# bolid-inputs-hv.net
KiCad netlist of a schematic drawn in Altium Designer
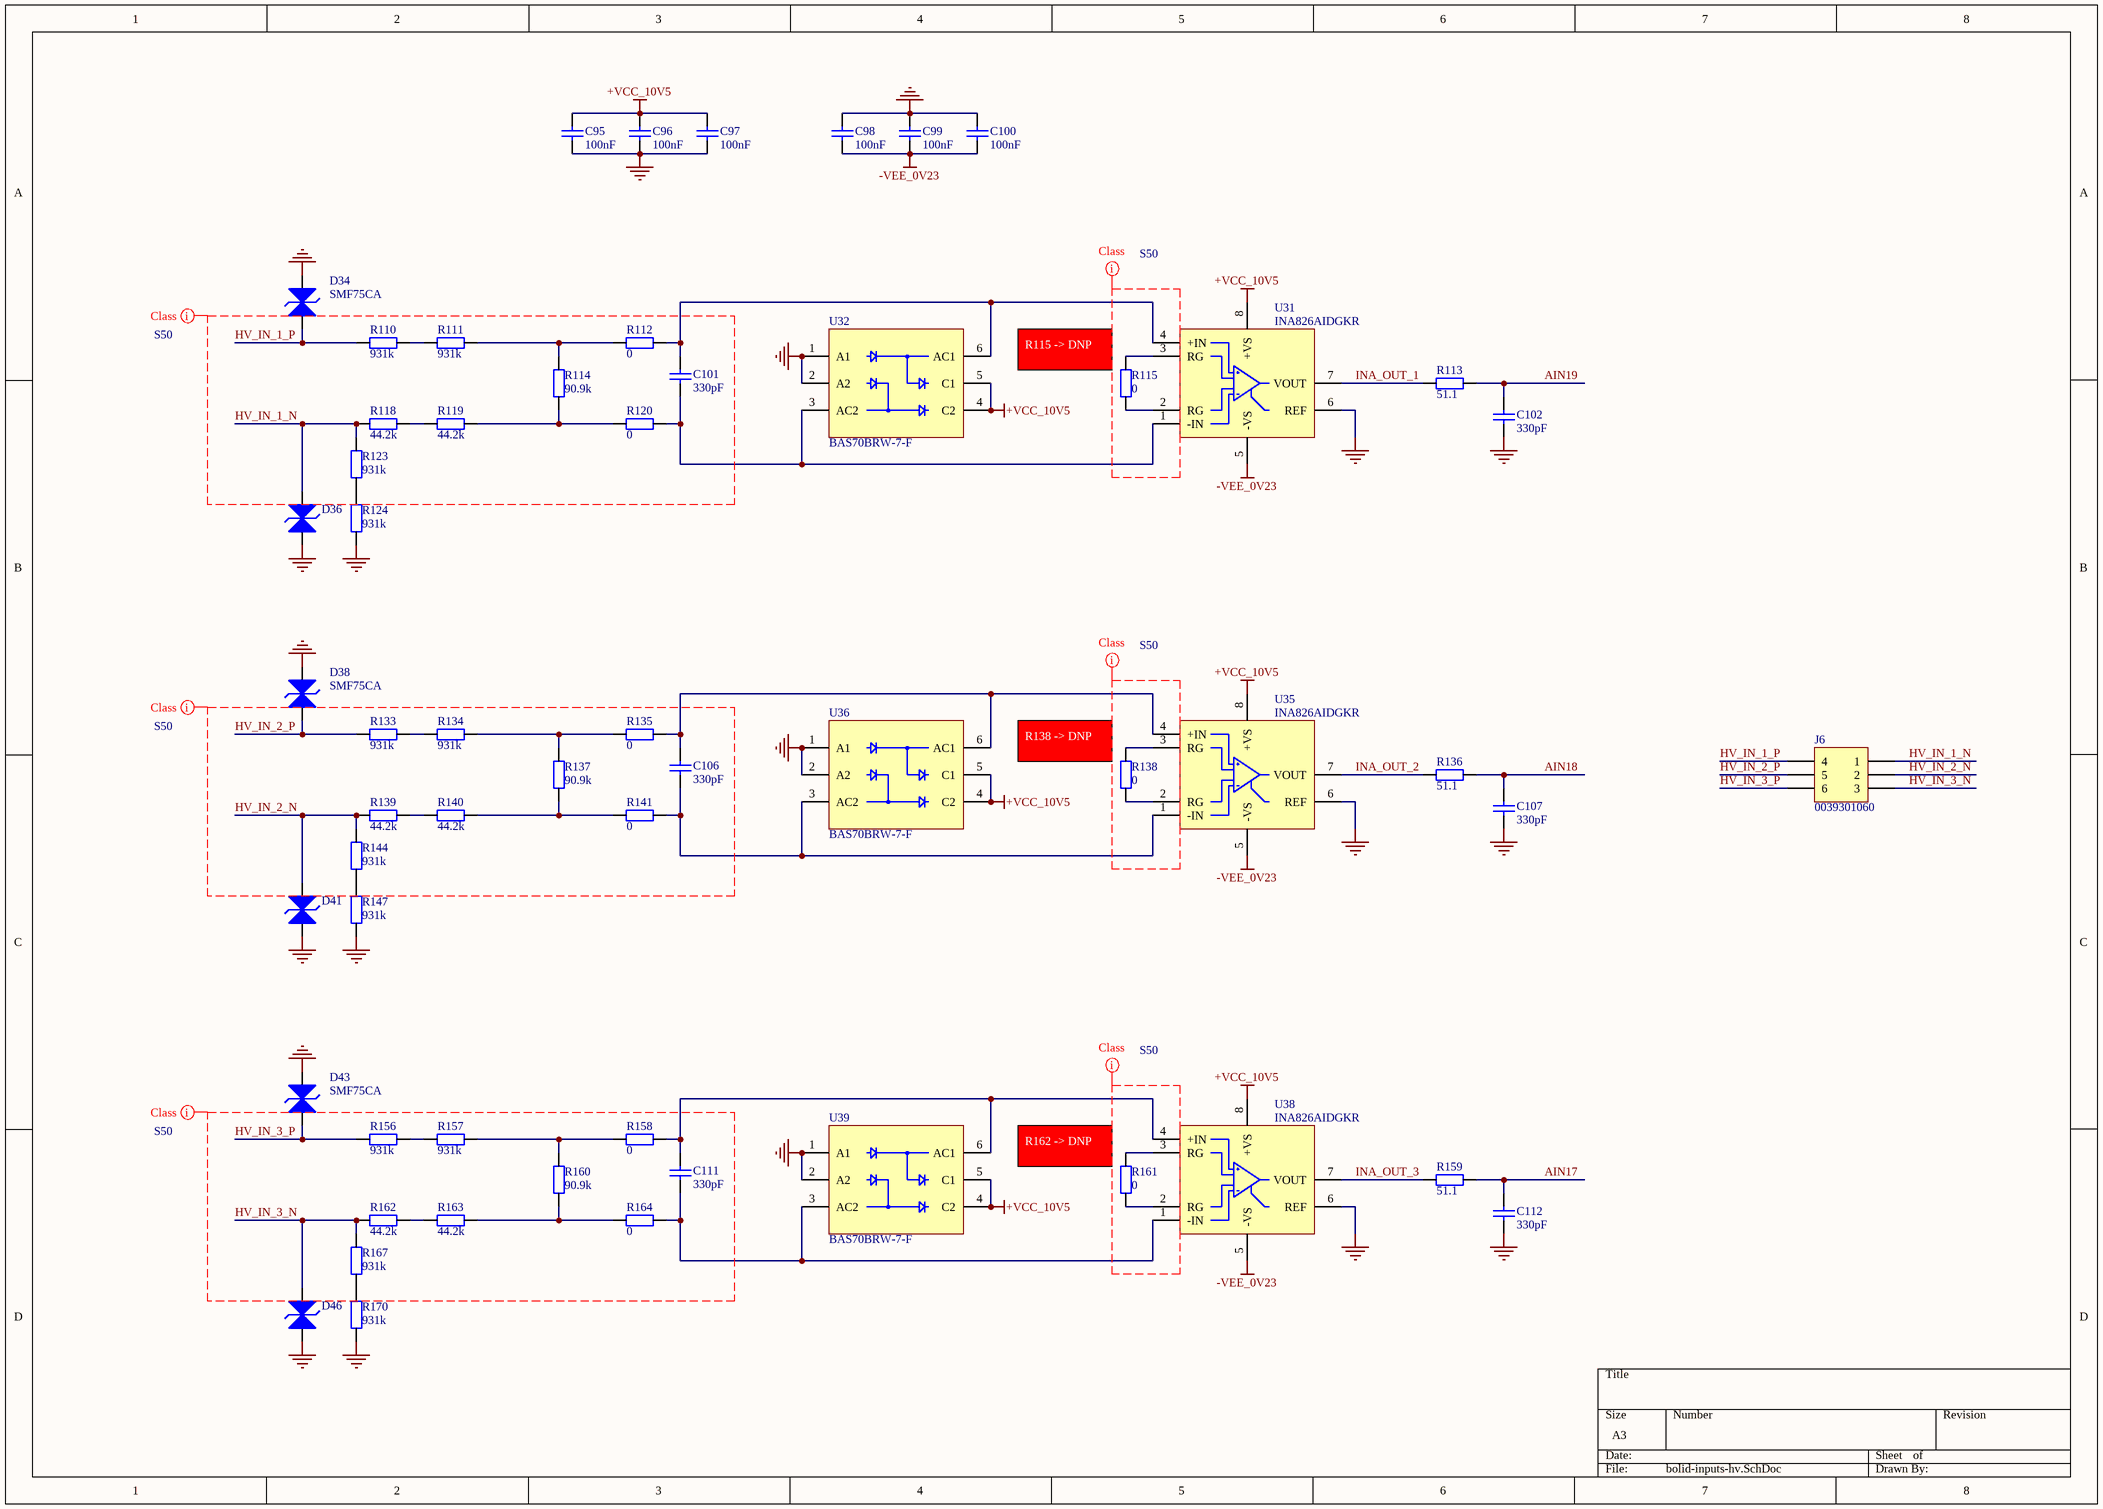
[diagram p0: bolid-inputs-hv.SchDoc]

(export (version "E")
  (design (tool "Eeschema 10.0.6"))
  (components
    (comp (ref "C95")
      (value "GRM155R71H104KE14D")
      (footprint "C0402-CAPC100X50X55L22 - Tayio Yuden TDK")
      (description "MLCC 0402 (1005) 100nF 10% 50V X7R")
      (fields
        (field (name "MANUFACTURER") "Murata Electronics")
        (field (name "TOLERANCE") "10 %")
        (field (name "VALUE DISPLAYED") "100nF")
      )
      (libsource (lib "capacitors2") (part "GRM155R71H104KE14D"))
    )
    (comp (ref "C96")
      (value "GRM155R71H104KE14D")
      (footprint "C0402-CAPC100X50X55L22 - Tayio Yuden TDK")
      (description "MLCC 0402 (1005) 100nF 10% 50V X7R")
      (fields
        (field (name "MANUFACTURER") "Murata Electronics")
        (field (name "TOLERANCE") "10 %")
        (field (name "VALUE DISPLAYED") "100nF")
      )
      (libsource (lib "capacitors2") (part "GRM155R71H104KE14D"))
    )
    (comp (ref "C97")
      (value "GRM155R71H104KE14D")
      (footprint "C0402-CAPC100X50X55L22 - Tayio Yuden TDK")
      (description "MLCC 0402 (1005) 100nF 10% 50V X7R")
      (fields
        (field (name "MANUFACTURER") "Murata Electronics")
        (field (name "TOLERANCE") "10 %")
        (field (name "VALUE DISPLAYED") "100nF")
      )
      (libsource (lib "capacitors2") (part "GRM155R71H104KE14D"))
    )
    (comp (ref "C98")
      (value "GRM155R71H104KE14D")
      (footprint "C0402-CAPC100X50X55L22 - Tayio Yuden TDK")
      (description "MLCC 0402 (1005) 100nF 10% 50V X7R")
      (fields
        (field (name "MANUFACTURER") "Murata Electronics")
        (field (name "TOLERANCE") "10 %")
        (field (name "VALUE DISPLAYED") "100nF")
      )
      (libsource (lib "capacitors2") (part "GRM155R71H104KE14D"))
    )
    (comp (ref "C99")
      (value "GRM155R71H104KE14D")
      (footprint "C0402-CAPC100X50X55L22 - Tayio Yuden TDK")
      (description "MLCC 0402 (1005) 100nF 10% 50V X7R")
      (fields
        (field (name "MANUFACTURER") "Murata Electronics")
        (field (name "TOLERANCE") "10 %")
        (field (name "VALUE DISPLAYED") "100nF")
      )
      (libsource (lib "capacitors2") (part "GRM155R71H104KE14D"))
    )
    (comp (ref "C100")
      (value "GRM155R71H104KE14D")
      (footprint "C0402-CAPC100X50X55L22 - Tayio Yuden TDK")
      (description "MLCC 0402 (1005) 100nF 10% 50V X7R")
      (fields
        (field (name "MANUFACTURER") "Murata Electronics")
        (field (name "TOLERANCE") "10 %")
        (field (name "VALUE DISPLAYED") "100nF")
      )
      (libsource (lib "capacitors2") (part "GRM155R71H104KE14D"))
    )
    (comp (ref "C101")
      (value "C0402C331J5GAC")
      (footprint "C0402-CAPC100X50X55L22 - Tayio Yuden TDK")
      (description "MLCC 0402 (1005) 330pF 5% 50V C0G (N0P)")
      (fields
        (field (name "MANUFACTURER") "KEMET")
        (field (name "TOLERANCE") "5%")
        (field (name "VALUE DISPLAYED") "330pF")
      )
      (libsource (lib "capacitors2") (part "C0402C331J5GAC"))
    )
    (comp (ref "C102")
      (value "C0402C331J5GAC")
      (footprint "C0402-CAPC100X50X55L22 - Tayio Yuden TDK")
      (description "MLCC 0402 (1005) 330pF 5% 50V C0G (N0P)")
      (fields
        (field (name "MANUFACTURER") "KEMET")
        (field (name "TOLERANCE") "5%")
        (field (name "VALUE DISPLAYED") "330pF")
      )
      (libsource (lib "capacitors2") (part "C0402C331J5GAC"))
    )
    (comp (ref "C106")
      (value "C0402C331J5GAC")
      (footprint "C0402-CAPC100X50X55L22 - Tayio Yuden TDK")
      (description "MLCC 0402 (1005) 330pF 5% 50V C0G (N0P)")
      (fields
        (field (name "MANUFACTURER") "KEMET")
        (field (name "TOLERANCE") "5%")
        (field (name "VALUE DISPLAYED") "330pF")
      )
      (libsource (lib "capacitors2") (part "C0402C331J5GAC"))
    )
    (comp (ref "C107")
      (value "C0402C331J5GAC")
      (footprint "C0402-CAPC100X50X55L22 - Tayio Yuden TDK")
      (description "MLCC 0402 (1005) 330pF 5% 50V C0G (N0P)")
      (fields
        (field (name "MANUFACTURER") "KEMET")
        (field (name "TOLERANCE") "5%")
        (field (name "VALUE DISPLAYED") "330pF")
      )
      (libsource (lib "capacitors2") (part "C0402C331J5GAC"))
    )
    (comp (ref "C111")
      (value "C0402C331J5GAC")
      (footprint "C0402-CAPC100X50X55L22 - Tayio Yuden TDK")
      (description "MLCC 0402 (1005) 330pF 5% 50V C0G (N0P)")
      (fields
        (field (name "MANUFACTURER") "KEMET")
        (field (name "TOLERANCE") "5%")
        (field (name "VALUE DISPLAYED") "330pF")
      )
      (libsource (lib "capacitors2") (part "C0402C331J5GAC"))
    )
    (comp (ref "C112")
      (value "C0402C331J5GAC")
      (footprint "C0402-CAPC100X50X55L22 - Tayio Yuden TDK")
      (description "MLCC 0402 (1005) 330pF 5% 50V C0G (N0P)")
      (fields
        (field (name "MANUFACTURER") "KEMET")
        (field (name "TOLERANCE") "5%")
        (field (name "VALUE DISPLAYED") "330pF")
      )
      (libsource (lib "capacitors2") (part "C0402C331J5GAC"))
    )
    (comp (ref "D34")
      (value "SMF75CA")
      (footprint "SOD-123FL SODFL365X110-2N - BIDIRECTIONAL - Littelfuse")
      (fields (field (name "MANUFACTURER") "Littelfuse"))
      (libsource (lib "semiconductors2") (part "SMF75CA"))
    )
    (comp (ref "D36")
      (value "SMF75CA")
      (footprint "SOD-123FL SODFL365X110-2N - BIDIRECTIONAL - Littelfuse")
      (fields (field (name "MANUFACTURER") "Littelfuse"))
      (libsource (lib "semiconductors2") (part "SMF75CA"))
    )
    (comp (ref "D38")
      (value "SMF75CA")
      (footprint "SOD-123FL SODFL365X110-2N - BIDIRECTIONAL - Littelfuse")
      (fields (field (name "MANUFACTURER") "Littelfuse"))
      (libsource (lib "semiconductors2") (part "SMF75CA"))
    )
    (comp (ref "D41")
      (value "SMF75CA")
      (footprint "SOD-123FL SODFL365X110-2N - BIDIRECTIONAL - Littelfuse")
      (fields (field (name "MANUFACTURER") "Littelfuse"))
      (libsource (lib "semiconductors2") (part "SMF75CA"))
    )
    (comp (ref "D43")
      (value "SMF75CA")
      (footprint "SOD-123FL SODFL365X110-2N - BIDIRECTIONAL - Littelfuse")
      (fields (field (name "MANUFACTURER") "Littelfuse"))
      (libsource (lib "semiconductors2") (part "SMF75CA"))
    )
    (comp (ref "D46")
      (value "SMF75CA")
      (footprint "SOD-123FL SODFL365X110-2N - BIDIRECTIONAL - Littelfuse")
      (fields (field (name "MANUFACTURER") "Littelfuse"))
      (libsource (lib "semiconductors2") (part "SMF75CA"))
    )
    (comp (ref "J6")
      (value "0039301060")
      (footprint "MOLEX Mini-Fit Jr 039301060 2x3 PEG")
      (fields (field (name "MANUFACTURER") "Molex"))
      (libsource (lib "connectors2") (part "039301060"))
    )
    (comp (ref "R110")
      (value "931k")
      (footprint "R0603-RESC160X80X55L30N")
      (description "RES 0603 (1608) 931.0k 1% 0.100W 50V Thick Film")
      (fields
        (field (name "MANUFACTURER") "Yageo")
        (field (name "MANUFACTURER PART NUMBER") "RC0603FR-07931KL")
      )
      (libsource (lib "resistors2") (part "RC0603FR-07931KL"))
    )
    (comp (ref "R111")
      (value "931k")
      (footprint "R0603-RESC160X80X55L30N")
      (description "RES 0603 (1608) 931.0k 1% 0.100W 50V Thick Film")
      (fields
        (field (name "MANUFACTURER") "Yageo")
        (field (name "MANUFACTURER PART NUMBER") "RC0603FR-07931KL")
      )
      (libsource (lib "resistors2") (part "RC0603FR-07931KL"))
    )
    (comp (ref "R112")
      (value "0")
      (footprint "R0402-RESC100X50X40L22N")
      (description "RES 0402 (1005) 0.00 ohm 1% 0.0625W 50V Thick Film")
      (fields
        (field (name "MANUFACTURER") "Yageo")
        (field (name "MANUFACTURER PART NUMBER") "RC0402JR-7D0RL")
      )
      (libsource (lib "resistors2") (part "RC0402JR-7D0RL"))
    )
    (comp (ref "R113")
      (value "51.1")
      (footprint "R0402-RESC100X50X40L22N")
      (description "RES 0402 (1005) 51.1 ohm 1% 0.0625W 50V Thick Film")
      (fields
        (field (name "MANUFACTURER") "Yageo")
        (field (name "MANUFACTURER PART NUMBER") "AC0402FR-0751R1L")
      )
      (libsource (lib "resistors2") (part "AC0402FR-0751R1L"))
    )
    (comp (ref "R114")
      (value "90.9k")
      (footprint "R0402-RESC100X50X40L22N")
      (description "RES 0402 (1005) 90.9k 1% 0.0625W 50V Thick Film")
      (fields
        (field (name "MANUFACTURER") "YAGEO")
        (field (name "MANUFACTURER PART NUMBER") "RC0402FR-0790K9L")
      )
      (libsource (lib "resistors2") (part "RC0402FR-0790K9L"))
    )
    (comp (ref "R115")
      (value "0")
      (footprint "R0402-RESC100X50X40L22N")
      (description "RES 0402 (1005) 0.00 ohm 1% 0.0625W 50V Thick Film")
      (fields
        (field (name "MANUFACTURER") "Yageo")
        (field (name "MANUFACTURER PART NUMBER") "RC0402JR-7D0RL")
      )
      (libsource (lib "") (part "RC0402JR-7D0RL_1"))
    )
    (comp (ref "R118")
      (value "44.2k")
      (footprint "R0603-RESC160X80X55L30N")
      (description "RES 0603 (1608) 44.2k 1% 0.100W 50V Thick Film")
      (fields
        (field (name "MANUFACTURER") "Yageo")
        (field (name "MANUFACTURER PART NUMBER") "RC0603FR-0744K2L")
      )
      (libsource (lib "resistors2") (part "RC0603FR-0744K2L"))
    )
    (comp (ref "R119")
      (value "44.2k")
      (footprint "R0603-RESC160X80X55L30N")
      (description "RES 0603 (1608) 44.2k 1% 0.100W 50V Thick Film")
      (fields
        (field (name "MANUFACTURER") "Yageo")
        (field (name "MANUFACTURER PART NUMBER") "RC0603FR-0744K2L")
      )
      (libsource (lib "resistors2") (part "RC0603FR-0744K2L"))
    )
    (comp (ref "R120")
      (value "0")
      (footprint "R0402-RESC100X50X40L22N")
      (description "RES 0402 (1005) 0.00 ohm 1% 0.0625W 50V Thick Film")
      (fields
        (field (name "MANUFACTURER") "Yageo")
        (field (name "MANUFACTURER PART NUMBER") "RC0402JR-7D0RL")
      )
      (libsource (lib "resistors2") (part "RC0402JR-7D0RL"))
    )
    (comp (ref "R123")
      (value "931k")
      (footprint "R0603-RESC160X80X55L30N")
      (description "RES 0603 (1608) 931.0k 1% 0.100W 50V Thick Film")
      (fields
        (field (name "MANUFACTURER") "Yageo")
        (field (name "MANUFACTURER PART NUMBER") "RC0603FR-07931KL")
      )
      (libsource (lib "") (part "RC0603FR-07931KL_1"))
    )
    (comp (ref "R124")
      (value "931k")
      (footprint "R0603-RESC160X80X55L30N")
      (description "RES 0603 (1608) 931.0k 1% 0.100W 50V Thick Film")
      (fields
        (field (name "MANUFACTURER") "Yageo")
        (field (name "MANUFACTURER PART NUMBER") "RC0603FR-07931KL")
      )
      (libsource (lib "") (part "RC0603FR-07931KL_1"))
    )
    (comp (ref "R133")
      (value "931k")
      (footprint "R0603-RESC160X80X55L30N")
      (description "RES 0603 (1608) 931.0k 1% 0.100W 50V Thick Film")
      (fields
        (field (name "MANUFACTURER") "Yageo")
        (field (name "MANUFACTURER PART NUMBER") "RC0603FR-07931KL")
      )
      (libsource (lib "resistors2") (part "RC0603FR-07931KL"))
    )
    (comp (ref "R134")
      (value "931k")
      (footprint "R0603-RESC160X80X55L30N")
      (description "RES 0603 (1608) 931.0k 1% 0.100W 50V Thick Film")
      (fields
        (field (name "MANUFACTURER") "Yageo")
        (field (name "MANUFACTURER PART NUMBER") "RC0603FR-07931KL")
      )
      (libsource (lib "resistors2") (part "RC0603FR-07931KL"))
    )
    (comp (ref "R135")
      (value "0")
      (footprint "R0402-RESC100X50X40L22N")
      (description "RES 0402 (1005) 0.00 ohm 1% 0.0625W 50V Thick Film")
      (fields
        (field (name "MANUFACTURER") "Yageo")
        (field (name "MANUFACTURER PART NUMBER") "RC0402JR-7D0RL")
      )
      (libsource (lib "resistors2") (part "RC0402JR-7D0RL"))
    )
    (comp (ref "R136")
      (value "51.1")
      (footprint "R0402-RESC100X50X40L22N")
      (description "RES 0402 (1005) 51.1 ohm 1% 0.0625W 50V Thick Film")
      (fields
        (field (name "MANUFACTURER") "Yageo")
        (field (name "MANUFACTURER PART NUMBER") "AC0402FR-0751R1L")
      )
      (libsource (lib "resistors2") (part "AC0402FR-0751R1L"))
    )
    (comp (ref "R137")
      (value "90.9k")
      (footprint "R0402-RESC100X50X40L22N")
      (description "RES 0402 (1005) 90.9k 1% 0.0625W 50V Thick Film")
      (fields
        (field (name "MANUFACTURER") "YAGEO")
        (field (name "MANUFACTURER PART NUMBER") "RC0402FR-0790K9L")
      )
      (libsource (lib "resistors2") (part "RC0402FR-0790K9L"))
    )
    (comp (ref "R138")
      (value "0")
      (footprint "R0402-RESC100X50X40L22N")
      (description "RES 0402 (1005) 0.00 ohm 1% 0.0625W 50V Thick Film")
      (fields
        (field (name "MANUFACTURER") "Yageo")
        (field (name "MANUFACTURER PART NUMBER") "RC0402JR-7D0RL")
      )
      (libsource (lib "") (part "RC0402JR-7D0RL_1"))
    )
    (comp (ref "R139")
      (value "44.2k")
      (footprint "R0603-RESC160X80X55L30N")
      (description "RES 0603 (1608) 44.2k 1% 0.100W 50V Thick Film")
      (fields
        (field (name "MANUFACTURER") "Yageo")
        (field (name "MANUFACTURER PART NUMBER") "RC0603FR-0744K2L")
      )
      (libsource (lib "resistors2") (part "RC0603FR-0744K2L"))
    )
    (comp (ref "R140")
      (value "44.2k")
      (footprint "R0603-RESC160X80X55L30N")
      (description "RES 0603 (1608) 44.2k 1% 0.100W 50V Thick Film")
      (fields
        (field (name "MANUFACTURER") "Yageo")
        (field (name "MANUFACTURER PART NUMBER") "RC0603FR-0744K2L")
      )
      (libsource (lib "resistors2") (part "RC0603FR-0744K2L"))
    )
    (comp (ref "R141")
      (value "0")
      (footprint "R0402-RESC100X50X40L22N")
      (description "RES 0402 (1005) 0.00 ohm 1% 0.0625W 50V Thick Film")
      (fields
        (field (name "MANUFACTURER") "Yageo")
        (field (name "MANUFACTURER PART NUMBER") "RC0402JR-7D0RL")
      )
      (libsource (lib "resistors2") (part "RC0402JR-7D0RL"))
    )
    (comp (ref "R144")
      (value "931k")
      (footprint "R0603-RESC160X80X55L30N")
      (description "RES 0603 (1608) 931.0k 1% 0.100W 50V Thick Film")
      (fields
        (field (name "MANUFACTURER") "Yageo")
        (field (name "MANUFACTURER PART NUMBER") "RC0603FR-07931KL")
      )
      (libsource (lib "") (part "RC0603FR-07931KL_1"))
    )
    (comp (ref "R147")
      (value "931k")
      (footprint "R0603-RESC160X80X55L30N")
      (description "RES 0603 (1608) 931.0k 1% 0.100W 50V Thick Film")
      (fields
        (field (name "MANUFACTURER") "Yageo")
        (field (name "MANUFACTURER PART NUMBER") "RC0603FR-07931KL")
      )
      (libsource (lib "") (part "RC0603FR-07931KL_1"))
    )
    (comp (ref "R156")
      (value "931k")
      (footprint "R0603-RESC160X80X55L30N")
      (description "RES 0603 (1608) 931.0k 1% 0.100W 50V Thick Film")
      (fields
        (field (name "MANUFACTURER") "Yageo")
        (field (name "MANUFACTURER PART NUMBER") "RC0603FR-07931KL")
      )
      (libsource (lib "resistors2") (part "RC0603FR-07931KL"))
    )
    (comp (ref "R157")
      (value "931k")
      (footprint "R0603-RESC160X80X55L30N")
      (description "RES 0603 (1608) 931.0k 1% 0.100W 50V Thick Film")
      (fields
        (field (name "MANUFACTURER") "Yageo")
        (field (name "MANUFACTURER PART NUMBER") "RC0603FR-07931KL")
      )
      (libsource (lib "resistors2") (part "RC0603FR-07931KL"))
    )
    (comp (ref "R158")
      (value "0")
      (footprint "R0402-RESC100X50X40L22N")
      (description "RES 0402 (1005) 0.00 ohm 1% 0.0625W 50V Thick Film")
      (fields
        (field (name "MANUFACTURER") "Yageo")
        (field (name "MANUFACTURER PART NUMBER") "RC0402JR-7D0RL")
      )
      (libsource (lib "resistors2") (part "RC0402JR-7D0RL"))
    )
    (comp (ref "R159")
      (value "51.1")
      (footprint "R0402-RESC100X50X40L22N")
      (description "RES 0402 (1005) 51.1 ohm 1% 0.0625W 50V Thick Film")
      (fields
        (field (name "MANUFACTURER") "Yageo")
        (field (name "MANUFACTURER PART NUMBER") "AC0402FR-0751R1L")
      )
      (libsource (lib "resistors2") (part "AC0402FR-0751R1L"))
    )
    (comp (ref "R160")
      (value "90.9k")
      (footprint "R0402-RESC100X50X40L22N")
      (description "RES 0402 (1005) 90.9k 1% 0.0625W 50V Thick Film")
      (fields
        (field (name "MANUFACTURER") "YAGEO")
        (field (name "MANUFACTURER PART NUMBER") "RC0402FR-0790K9L")
      )
      (libsource (lib "resistors2") (part "RC0402FR-0790K9L"))
    )
    (comp (ref "R161")
      (value "0")
      (footprint "R0402-RESC100X50X40L22N")
      (description "RES 0402 (1005) 0.00 ohm 1% 0.0625W 50V Thick Film")
      (fields
        (field (name "MANUFACTURER") "Yageo")
        (field (name "MANUFACTURER PART NUMBER") "RC0402JR-7D0RL")
      )
      (libsource (lib "") (part "RC0402JR-7D0RL_1"))
    )
    (comp (ref "R162")
      (value "44.2k")
      (footprint "R0603-RESC160X80X55L30N")
      (description "RES 0603 (1608) 44.2k 1% 0.100W 50V Thick Film")
      (fields
        (field (name "MANUFACTURER") "Yageo")
        (field (name "MANUFACTURER PART NUMBER") "RC0603FR-0744K2L")
      )
      (libsource (lib "resistors2") (part "RC0603FR-0744K2L"))
    )
    (comp (ref "R163")
      (value "44.2k")
      (footprint "R0603-RESC160X80X55L30N")
      (description "RES 0603 (1608) 44.2k 1% 0.100W 50V Thick Film")
      (fields
        (field (name "MANUFACTURER") "Yageo")
        (field (name "MANUFACTURER PART NUMBER") "RC0603FR-0744K2L")
      )
      (libsource (lib "resistors2") (part "RC0603FR-0744K2L"))
    )
    (comp (ref "R164")
      (value "0")
      (footprint "R0402-RESC100X50X40L22N")
      (description "RES 0402 (1005) 0.00 ohm 1% 0.0625W 50V Thick Film")
      (fields
        (field (name "MANUFACTURER") "Yageo")
        (field (name "MANUFACTURER PART NUMBER") "RC0402JR-7D0RL")
      )
      (libsource (lib "resistors2") (part "RC0402JR-7D0RL"))
    )
    (comp (ref "R167")
      (value "931k")
      (footprint "R0603-RESC160X80X55L30N")
      (description "RES 0603 (1608) 931.0k 1% 0.100W 50V Thick Film")
      (fields
        (field (name "MANUFACTURER") "Yageo")
        (field (name "MANUFACTURER PART NUMBER") "RC0603FR-07931KL")
      )
      (libsource (lib "") (part "RC0603FR-07931KL_1"))
    )
    (comp (ref "R170")
      (value "931k")
      (footprint "R0603-RESC160X80X55L30N")
      (description "RES 0603 (1608) 931.0k 1% 0.100W 50V Thick Film")
      (fields
        (field (name "MANUFACTURER") "Yageo")
        (field (name "MANUFACTURER PART NUMBER") "RC0603FR-07931KL")
      )
      (libsource (lib "") (part "RC0603FR-07931KL_1"))
    )
    (comp (ref "U31")
      (value "INA826AIDGKR")
      (footprint "TI VSSOP8 DGK0008A TSOP65P490X110-8N")
      (description "Precision, 200-μA Supply Current, 36-V Supply Instrumentation Amplifier 8-VSSOP -40 to 125")
      (fields (field (name "MANUFACTURER") "Texas Instruments"))
      (libsource (lib "ics2") (part "INA826AIDGKR"))
    )
    (comp (ref "U32")
      (value "BAS70BRW-7-F")
      (footprint "SOT363 DIODES DS30158 Rev. 14-2 SOT65P210X110-6N")
      (description "BAS70BRW Series 70 V 100 mA Surface Mount Schottky Barrier Diode Arrays SOT-363")
      (fields (field (name "MANUFACTURER") "Diodes"))
      (libsource (lib "semiconductors2") (part "BAS70BRW-7-F"))
    )
    (comp (ref "U35")
      (value "INA826AIDGKR")
      (footprint "TI VSSOP8 DGK0008A TSOP65P490X110-8N")
      (description "Precision, 200-μA Supply Current, 36-V Supply Instrumentation Amplifier 8-VSSOP -40 to 125")
      (fields (field (name "MANUFACTURER") "Texas Instruments"))
      (libsource (lib "ics2") (part "INA826AIDGKR"))
    )
    (comp (ref "U36")
      (value "BAS70BRW-7-F")
      (footprint "SOT363 DIODES DS30158 Rev. 14-2 SOT65P210X110-6N")
      (description "BAS70BRW Series 70 V 100 mA Surface Mount Schottky Barrier Diode Arrays SOT-363")
      (fields (field (name "MANUFACTURER") "Diodes"))
      (libsource (lib "semiconductors2") (part "BAS70BRW-7-F"))
    )
    (comp (ref "U38")
      (value "INA826AIDGKR")
      (footprint "TI VSSOP8 DGK0008A TSOP65P490X110-8N")
      (description "Precision, 200-μA Supply Current, 36-V Supply Instrumentation Amplifier 8-VSSOP -40 to 125")
      (fields (field (name "MANUFACTURER") "Texas Instruments"))
      (libsource (lib "ics2") (part "INA826AIDGKR"))
    )
    (comp (ref "U39")
      (value "BAS70BRW-7-F")
      (footprint "SOT363 DIODES DS30158 Rev. 14-2 SOT65P210X110-6N")
      (description "BAS70BRW Series 70 V 100 mA Surface Mount Schottky Barrier Diode Arrays SOT-363")
      (fields (field (name "MANUFACTURER") "Diodes"))
      (libsource (lib "semiconductors2") (part "BAS70BRW-7-F"))
    )
  )
  (nets
    (net (code "1") (name "+VCC_10V5") (class "Default")
      (node (ref "C95") (pin "2") (pinfunction "2_2") (pintype "passive"))
      (node (ref "C96") (pin "2") (pinfunction "2_2") (pintype "passive"))
      (node (ref "C97") (pin "2") (pinfunction "2_2") (pintype "passive"))
      (node (ref "U31") (pin "8") (pinfunction "+VS_8") (pintype "passive"))
      (node (ref "U32") (pin "4") (pinfunction "C2_4") (pintype "passive"))
      (node (ref "U32") (pin "5") (pinfunction "C1_5") (pintype "passive"))
      (node (ref "U35") (pin "8") (pinfunction "+VS_8") (pintype "passive"))
      (node (ref "U36") (pin "4") (pinfunction "C2_4") (pintype "passive"))
      (node (ref "U36") (pin "5") (pinfunction "C1_5") (pintype "passive"))
      (node (ref "U38") (pin "8") (pinfunction "+VS_8") (pintype "passive"))
      (node (ref "U39") (pin "4") (pinfunction "C2_4") (pintype "passive"))
      (node (ref "U39") (pin "5") (pinfunction "C1_5") (pintype "passive"))
    )
    (net (code "2") (name "-VEE_0V23") (class "Default")
      (node (ref "C100") (pin "1") (pinfunction "1_1") (pintype "passive"))
      (node (ref "C98") (pin "1") (pinfunction "1_1") (pintype "passive"))
      (node (ref "C99") (pin "1") (pinfunction "1_1") (pintype "passive"))
      (node (ref "U31") (pin "5") (pinfunction "-VS_5") (pintype "passive"))
      (node (ref "U35") (pin "5") (pinfunction "-VS_5") (pintype "passive"))
      (node (ref "U38") (pin "5") (pinfunction "-VS_5") (pintype "passive"))
    )
    (net (code "3") (name "/AIN17") (class "Default")
      (node (ref "C112") (pin "2") (pinfunction "2_2") (pintype "passive"))
      (node (ref "R159") (pin "2") (pinfunction "2_2") (pintype "passive"))
    )
    (net (code "4") (name "/AIN18") (class "Default")
      (node (ref "C107") (pin "2") (pinfunction "2_2") (pintype "passive"))
      (node (ref "R136") (pin "2") (pinfunction "2_2") (pintype "passive"))
    )
    (net (code "5") (name "/AIN19") (class "Default")
      (node (ref "C102") (pin "2") (pinfunction "2_2") (pintype "passive"))
      (node (ref "R113") (pin "2") (pinfunction "2_2") (pintype "passive"))
    )
    (net (code "6") (name "/HV_IN_1_N") (class "Default")
      (node (ref "D36") (pin "2") (pinfunction "2_2") (pintype "passive"))
      (node (ref "J6") (pin "1") (pinfunction "1_1") (pintype "passive"))
      (node (ref "R118") (pin "1") (pinfunction "1_1") (pintype "passive"))
      (node (ref "R123") (pin "2") (pinfunction "2_2") (pintype "passive"))
    )
    (net (code "7") (name "/HV_IN_1_P") (class "Default")
      (node (ref "D34") (pin "1") (pinfunction "1_1") (pintype "passive"))
      (node (ref "J6") (pin "4") (pinfunction "4_4") (pintype "passive"))
      (node (ref "R110") (pin "1") (pinfunction "1_1") (pintype "passive"))
    )
    (net (code "8") (name "/HV_IN_2_N") (class "Default")
      (node (ref "D41") (pin "2") (pinfunction "2_2") (pintype "passive"))
      (node (ref "J6") (pin "2") (pinfunction "2_2") (pintype "passive"))
      (node (ref "R139") (pin "1") (pinfunction "1_1") (pintype "passive"))
      (node (ref "R144") (pin "2") (pinfunction "2_2") (pintype "passive"))
    )
    (net (code "9") (name "/HV_IN_2_P") (class "Default")
      (node (ref "D38") (pin "1") (pinfunction "1_1") (pintype "passive"))
      (node (ref "J6") (pin "5") (pinfunction "5_5") (pintype "passive"))
      (node (ref "R133") (pin "1") (pinfunction "1_1") (pintype "passive"))
    )
    (net (code "10") (name "/HV_IN_3_N") (class "Default")
      (node (ref "D46") (pin "2") (pinfunction "2_2") (pintype "passive"))
      (node (ref "J6") (pin "3") (pinfunction "3_3") (pintype "passive"))
      (node (ref "R162") (pin "1") (pinfunction "1_1") (pintype "passive"))
      (node (ref "R167") (pin "2") (pinfunction "2_2") (pintype "passive"))
    )
    (net (code "11") (name "/HV_IN_3_P") (class "Default")
      (node (ref "D43") (pin "1") (pinfunction "1_1") (pintype "passive"))
      (node (ref "J6") (pin "6") (pinfunction "6_6") (pintype "passive"))
      (node (ref "R156") (pin "1") (pinfunction "1_1") (pintype "passive"))
    )
    (net (code "12") (name "/INA_OUT_1") (class "Default")
      (node (ref "R113") (pin "1") (pinfunction "1_1") (pintype "passive"))
      (node (ref "U31") (pin "7") (pinfunction "VOUT_7") (pintype "passive"))
    )
    (net (code "13") (name "/INA_OUT_2") (class "Default")
      (node (ref "R136") (pin "1") (pinfunction "1_1") (pintype "passive"))
      (node (ref "U35") (pin "7") (pinfunction "VOUT_7") (pintype "passive"))
    )
    (net (code "14") (name "/INA_OUT_3") (class "Default")
      (node (ref "R159") (pin "1") (pinfunction "1_1") (pintype "passive"))
      (node (ref "U38") (pin "7") (pinfunction "VOUT_7") (pintype "passive"))
    )
    (net (code "15") (name "GND") (class "Default")
      (node (ref "C100") (pin "2") (pinfunction "2_2") (pintype "passive"))
      (node (ref "C102") (pin "1") (pinfunction "1_1") (pintype "passive"))
      (node (ref "C107") (pin "1") (pinfunction "1_1") (pintype "passive"))
      (node (ref "C112") (pin "1") (pinfunction "1_1") (pintype "passive"))
      (node (ref "C95") (pin "1") (pinfunction "1_1") (pintype "passive"))
      (node (ref "C96") (pin "1") (pinfunction "1_1") (pintype "passive"))
      (node (ref "C97") (pin "1") (pinfunction "1_1") (pintype "passive"))
      (node (ref "C98") (pin "2") (pinfunction "2_2") (pintype "passive"))
      (node (ref "C99") (pin "2") (pinfunction "2_2") (pintype "passive"))
      (node (ref "D34") (pin "2") (pinfunction "2_2") (pintype "passive"))
      (node (ref "D36") (pin "1") (pinfunction "1_1") (pintype "passive"))
      (node (ref "D38") (pin "2") (pinfunction "2_2") (pintype "passive"))
      (node (ref "D41") (pin "1") (pinfunction "1_1") (pintype "passive"))
      (node (ref "D43") (pin "2") (pinfunction "2_2") (pintype "passive"))
      (node (ref "D46") (pin "1") (pinfunction "1_1") (pintype "passive"))
      (node (ref "R124") (pin "1") (pinfunction "1_1") (pintype "passive"))
      (node (ref "R147") (pin "1") (pinfunction "1_1") (pintype "passive"))
      (node (ref "R170") (pin "1") (pinfunction "1_1") (pintype "passive"))
      (node (ref "U31") (pin "6") (pinfunction "REF_6") (pintype "passive"))
      (node (ref "U32") (pin "1") (pinfunction "A1_1") (pintype "passive"))
      (node (ref "U32") (pin "2") (pinfunction "A2_2") (pintype "passive"))
      (node (ref "U35") (pin "6") (pinfunction "REF_6") (pintype "passive"))
      (node (ref "U36") (pin "1") (pinfunction "A1_1") (pintype "passive"))
      (node (ref "U36") (pin "2") (pinfunction "A2_2") (pintype "passive"))
      (node (ref "U38") (pin "6") (pinfunction "REF_6") (pintype "passive"))
      (node (ref "U39") (pin "1") (pinfunction "A1_1") (pintype "passive"))
      (node (ref "U39") (pin "2") (pinfunction "A2_2") (pintype "passive"))
    )
    (net (code "16") (name "Net-(R110-Pad2)") (class "Default")
      (node (ref "R110") (pin "2") (pinfunction "2_2") (pintype "passive"))
      (node (ref "R111") (pin "1") (pinfunction "1_1") (pintype "passive"))
    )
    (net (code "17") (name "Net-(R111-Pad2)") (class "Default")
      (node (ref "R111") (pin "2") (pinfunction "2_2") (pintype "passive"))
      (node (ref "R112") (pin "2") (pinfunction "2_2") (pintype "passive"))
      (node (ref "R114") (pin "2") (pinfunction "2_2") (pintype "passive"))
    )
    (net (code "18") (name "Net-(R114-Pad1)") (class "Default")
      (node (ref "R114") (pin "1") (pinfunction "1_1") (pintype "passive"))
      (node (ref "R119") (pin "2") (pinfunction "2_2") (pintype "passive"))
      (node (ref "R120") (pin "2") (pinfunction "2_2") (pintype "passive"))
    )
    (net (code "19") (name "Net-(R115-Pad1)") (class "Default")
      (node (ref "R115") (pin "1") (pinfunction "1_1") (pintype "passive"))
      (node (ref "U31") (pin "2") (pinfunction "RG_2") (pintype "passive"))
    )
    (net (code "20") (name "Net-(R115-Pad2)") (class "Default")
      (node (ref "R115") (pin "2") (pinfunction "2_2") (pintype "passive"))
      (node (ref "U31") (pin "3") (pinfunction "RG_3") (pintype "passive"))
    )
    (net (code "21") (name "Net-(R118-Pad2)") (class "Default")
      (node (ref "R118") (pin "2") (pinfunction "2_2") (pintype "passive"))
      (node (ref "R119") (pin "1") (pinfunction "1_1") (pintype "passive"))
    )
    (net (code "22") (name "Net-(R123-Pad1)") (class "Default")
      (node (ref "R123") (pin "1") (pinfunction "1_1") (pintype "passive"))
      (node (ref "R124") (pin "2") (pinfunction "2_2") (pintype "passive"))
    )
    (net (code "23") (name "Net-(R133-Pad2)") (class "Default")
      (node (ref "R133") (pin "2") (pinfunction "2_2") (pintype "passive"))
      (node (ref "R134") (pin "1") (pinfunction "1_1") (pintype "passive"))
    )
    (net (code "24") (name "Net-(R134-Pad2)") (class "Default")
      (node (ref "R134") (pin "2") (pinfunction "2_2") (pintype "passive"))
      (node (ref "R135") (pin "2") (pinfunction "2_2") (pintype "passive"))
      (node (ref "R137") (pin "2") (pinfunction "2_2") (pintype "passive"))
    )
    (net (code "25") (name "Net-(R137-Pad1)") (class "Default")
      (node (ref "R137") (pin "1") (pinfunction "1_1") (pintype "passive"))
      (node (ref "R140") (pin "2") (pinfunction "2_2") (pintype "passive"))
      (node (ref "R141") (pin "2") (pinfunction "2_2") (pintype "passive"))
    )
    (net (code "26") (name "Net-(R138-Pad1)") (class "Default")
      (node (ref "R138") (pin "1") (pinfunction "1_1") (pintype "passive"))
      (node (ref "U35") (pin "2") (pinfunction "RG_2") (pintype "passive"))
    )
    (net (code "27") (name "Net-(R138-Pad2)") (class "Default")
      (node (ref "R138") (pin "2") (pinfunction "2_2") (pintype "passive"))
      (node (ref "U35") (pin "3") (pinfunction "RG_3") (pintype "passive"))
    )
    (net (code "28") (name "Net-(R139-Pad2)") (class "Default")
      (node (ref "R139") (pin "2") (pinfunction "2_2") (pintype "passive"))
      (node (ref "R140") (pin "1") (pinfunction "1_1") (pintype "passive"))
    )
    (net (code "29") (name "Net-(R144-Pad1)") (class "Default")
      (node (ref "R144") (pin "1") (pinfunction "1_1") (pintype "passive"))
      (node (ref "R147") (pin "2") (pinfunction "2_2") (pintype "passive"))
    )
    (net (code "30") (name "Net-(R156-Pad2)") (class "Default")
      (node (ref "R156") (pin "2") (pinfunction "2_2") (pintype "passive"))
      (node (ref "R157") (pin "1") (pinfunction "1_1") (pintype "passive"))
    )
    (net (code "31") (name "Net-(R157-Pad2)") (class "Default")
      (node (ref "R157") (pin "2") (pinfunction "2_2") (pintype "passive"))
      (node (ref "R158") (pin "2") (pinfunction "2_2") (pintype "passive"))
      (node (ref "R160") (pin "2") (pinfunction "2_2") (pintype "passive"))
    )
    (net (code "32") (name "Net-(R160-Pad1)") (class "Default")
      (node (ref "R160") (pin "1") (pinfunction "1_1") (pintype "passive"))
      (node (ref "R163") (pin "2") (pinfunction "2_2") (pintype "passive"))
      (node (ref "R164") (pin "2") (pinfunction "2_2") (pintype "passive"))
    )
    (net (code "33") (name "Net-(R161-Pad1)") (class "Default")
      (node (ref "R161") (pin "1") (pinfunction "1_1") (pintype "passive"))
      (node (ref "U38") (pin "2") (pinfunction "RG_2") (pintype "passive"))
    )
    (net (code "34") (name "Net-(R161-Pad2)") (class "Default")
      (node (ref "R161") (pin "2") (pinfunction "2_2") (pintype "passive"))
      (node (ref "U38") (pin "3") (pinfunction "RG_3") (pintype "passive"))
    )
    (net (code "35") (name "Net-(R162-Pad2)") (class "Default")
      (node (ref "R162") (pin "2") (pinfunction "2_2") (pintype "passive"))
      (node (ref "R163") (pin "1") (pinfunction "1_1") (pintype "passive"))
    )
    (net (code "36") (name "Net-(R167-Pad1)") (class "Default")
      (node (ref "R167") (pin "1") (pinfunction "1_1") (pintype "passive"))
      (node (ref "R170") (pin "2") (pinfunction "2_2") (pintype "passive"))
    )
    (net (code "37") (name "Net-(U31-+IN)") (class "Default")
      (node (ref "C101") (pin "2") (pinfunction "2_2") (pintype "passive"))
      (node (ref "R112") (pin "1") (pinfunction "1_1") (pintype "passive"))
      (node (ref "U31") (pin "4") (pinfunction "+IN_4") (pintype "passive"))
      (node (ref "U32") (pin "6") (pinfunction "AC1_6") (pintype "passive"))
    )
    (net (code "38") (name "Net-(U31--IN)") (class "Default")
      (node (ref "C101") (pin "1") (pinfunction "1_1") (pintype "passive"))
      (node (ref "R120") (pin "1") (pinfunction "1_1") (pintype "passive"))
      (node (ref "U31") (pin "1") (pinfunction "-IN_1") (pintype "passive"))
      (node (ref "U32") (pin "3") (pinfunction "AC2_3") (pintype "passive"))
    )
    (net (code "39") (name "Net-(U35-+IN)") (class "Default")
      (node (ref "C106") (pin "2") (pinfunction "2_2") (pintype "passive"))
      (node (ref "R135") (pin "1") (pinfunction "1_1") (pintype "passive"))
      (node (ref "U35") (pin "4") (pinfunction "+IN_4") (pintype "passive"))
      (node (ref "U36") (pin "6") (pinfunction "AC1_6") (pintype "passive"))
    )
    (net (code "40") (name "Net-(U35--IN)") (class "Default")
      (node (ref "C106") (pin "1") (pinfunction "1_1") (pintype "passive"))
      (node (ref "R141") (pin "1") (pinfunction "1_1") (pintype "passive"))
      (node (ref "U35") (pin "1") (pinfunction "-IN_1") (pintype "passive"))
      (node (ref "U36") (pin "3") (pinfunction "AC2_3") (pintype "passive"))
    )
    (net (code "41") (name "Net-(U38-+IN)") (class "Default")
      (node (ref "C111") (pin "2") (pinfunction "2_2") (pintype "passive"))
      (node (ref "R158") (pin "1") (pinfunction "1_1") (pintype "passive"))
      (node (ref "U38") (pin "4") (pinfunction "+IN_4") (pintype "passive"))
      (node (ref "U39") (pin "6") (pinfunction "AC1_6") (pintype "passive"))
    )
    (net (code "42") (name "Net-(U38--IN)") (class "Default")
      (node (ref "C111") (pin "1") (pinfunction "1_1") (pintype "passive"))
      (node (ref "R164") (pin "1") (pinfunction "1_1") (pintype "passive"))
      (node (ref "U38") (pin "1") (pinfunction "-IN_1") (pintype "passive"))
      (node (ref "U39") (pin "3") (pinfunction "AC2_3") (pintype "passive"))
    )
  )
)
